# 28_-_PWR_IN_MECH_DOC.net
KiCad netlist of a schematic drawn in Altium Designer
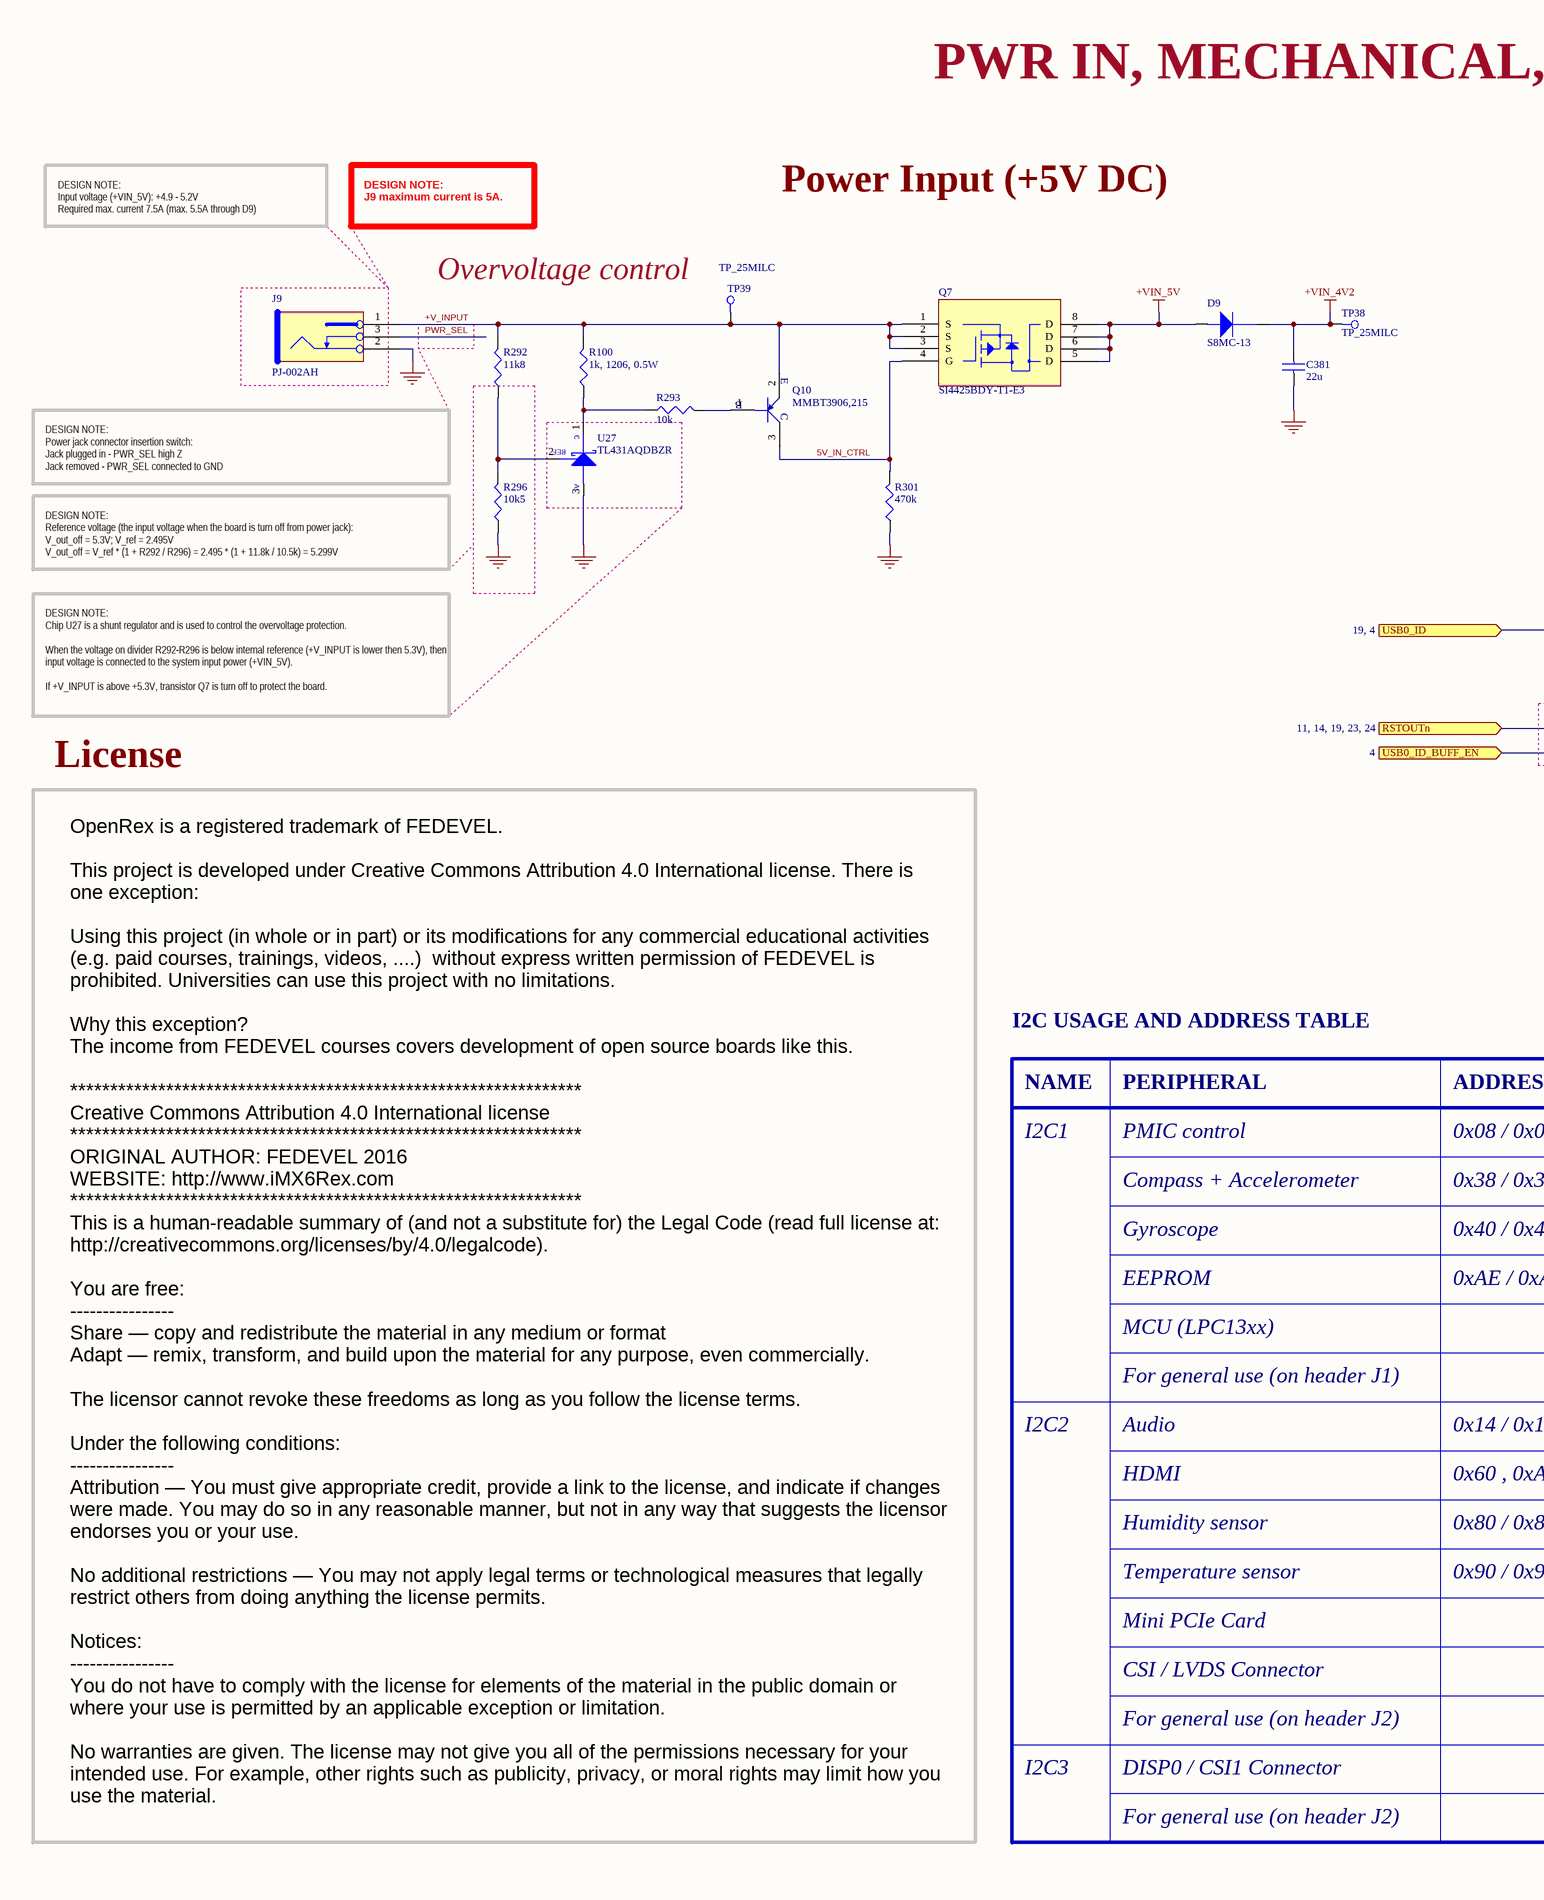
[diagram p0: [28] - PWR IN, MECH, DOC.SchDoc, left]
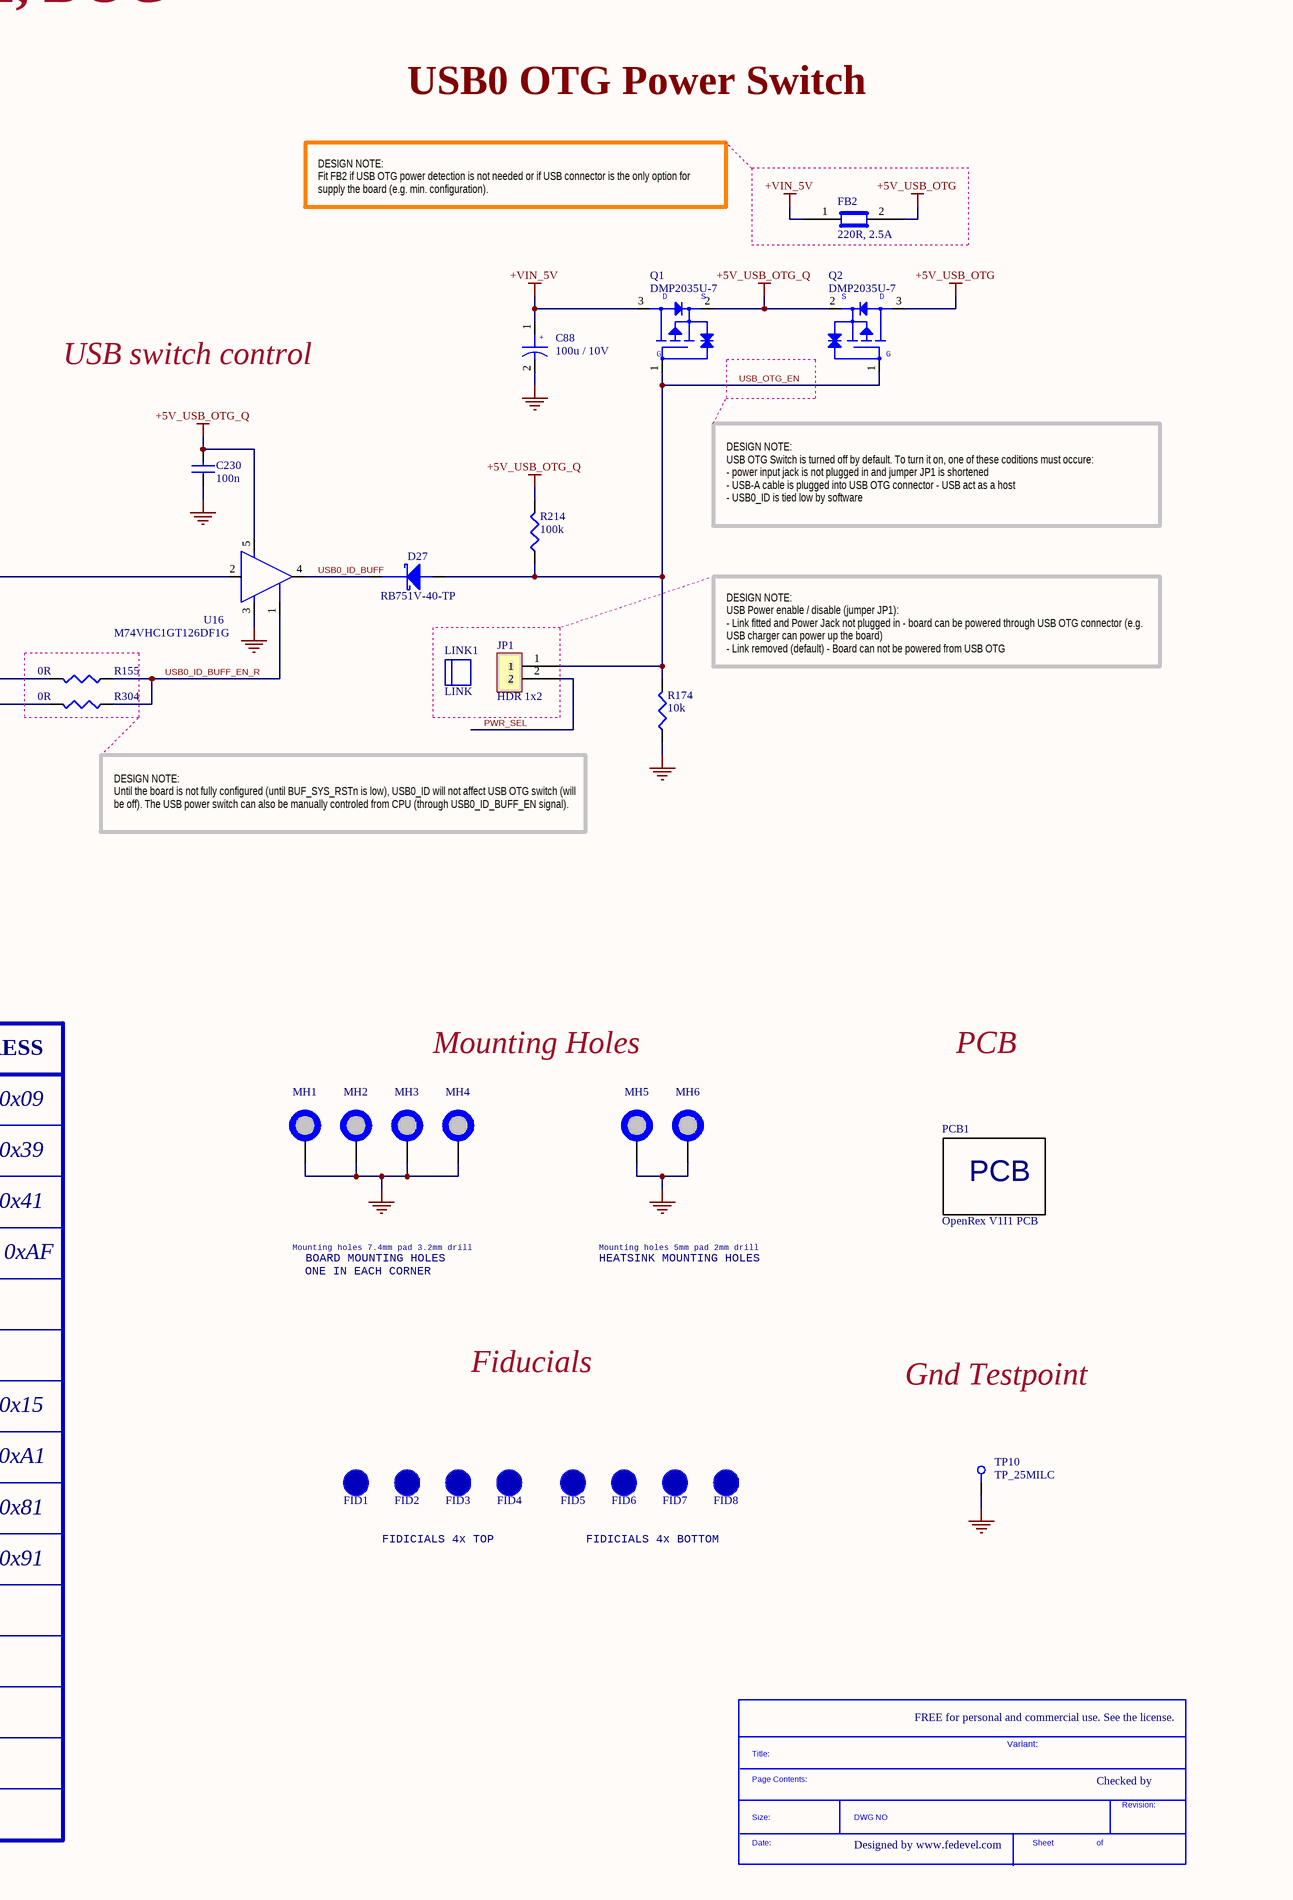
[diagram p1: [28] - PWR IN, MECH, DOC.SchDoc, right]

(export (version "E")
  (design (tool "Eeschema 10.0.6"))
  (components
    (comp (ref "C88")
      (value "100u / 10V")
      (footprint "C2312")
      (description "CAP TANT 100UF 10V 10% 2312")
      (fields
        (field (name "MANUFACTURER") "AVX Corporation")
        (field (name "MANUFACTURER PART NUMBER") "TPSC107K010R0150")
        (field (name ".CREATOR") "MM")
        (field (name ".CHECKED PCB") "MM")
        (field (name ".CHECKED SCH") "MM")
      )
      (libsource (lib "Integrated_Library_FEDEVEL_APR_2015") (part "TPSC107K010R0150"))
    )
    (comp (ref "C230")
      (value "100n")
      (footprint "C0402")
      (description "CAP CER .10UF 50V X5R 10% 0402")
      (fields
        (field (name "MANUFACTURER") "TDK Corporation")
        (field (name "MANUFACTURER PART NUMBER") "C1005X5R1H104K")
      )
      (libsource (lib "Integrated_Library_FEDEVEL_APR_2015") (part "C1005X5R1H104K"))
    )
    (comp (ref "C381")
      (value "22u")
      (footprint "C0603")
      (description "CAP CER 22UF 6.3V 20% X5R 0603")
      (fields
        (field (name "MANUFACTURER") "TDK Corporation")
        (field (name "MANUFACTURER PART NUMBER") "C1608X5R0J226M080AC")
        (field (name ".CREATOR") "MM")
        (field (name ".CHECKED PCB") "MM")
        (field (name ".CHECKED SCH") "MM")
      )
      (libsource (lib "Integrated_Library_FEDEVEL_APR_2015") (part "C1608X5R0J226M080AC"))
    )
    (comp (ref "D9")
      (value "S8MC-13")
      (footprint "SMC")
      (description "DIODE GEN PURP 1KV 8A SMC")
      (fields
        (field (name "MANUFACTURER") "Diodes Incorporated")
        (field (name ".CHECKED PCB") "MM")
        (field (name ".CHECKED SCH") "MM")
        (field (name ".CREATOR") "MM")
      )
      (libsource (lib "Integrated_Library_FEDEVEL_APR_2015") (part "S8MC-13"))
    )
    (comp (ref "D27")
      (value "RB751V-40-TP")
      (footprint "SOD323")
      (description "DIODE SCHTKY 30MA 30V SOD-323")
      (fields (field (name "MANUFACTURER") "Micro Commercial Co"))
      (libsource (lib "Integrated_Library_FEDEVEL_APR_2015") (part "RB751V-40-TP"))
    )
    (comp (ref "FB2")
      (value "220R, 2.5A")
      (footprint "C0603")
      (description "FERRITE CHIP 220 OHM 2500MA 0603")
      (fields
        (field (name "MANUFACTURER") "Murata Electronics North America")
        (field (name "MANUFACTURER PART NUMBER") "BLM18SG221TN1D")
      )
      (libsource (lib "Integrated_Library_FEDEVEL_APR_2015") (part "BLM18SG221TN1D"))
    )
    (comp (ref "FID1")
      (value "FID_1MM_SMALL")
      (footprint "FID_40X52D")
      (description "Fiducial 40mil Diameter, 52mil Mask")
      (libsource (lib "Integrated_Library_FEDEVEL_APR_2015") (part "FID_1MM_SMALL"))
    )
    (comp (ref "FID2")
      (value "FID_1MM_SMALL")
      (footprint "FID_40X52D")
      (description "Fiducial 40mil Diameter, 52mil Mask")
      (libsource (lib "Integrated_Library_FEDEVEL_APR_2015") (part "FID_1MM_SMALL"))
    )
    (comp (ref "FID3")
      (value "FID_1MM_SMALL")
      (footprint "FID_40X52D")
      (description "Fiducial 40mil Diameter, 52mil Mask")
      (libsource (lib "Integrated_Library_FEDEVEL_APR_2015") (part "FID_1MM_SMALL"))
    )
    (comp (ref "FID4")
      (value "FID_1MM_SMALL")
      (footprint "FID_40X52D")
      (description "Fiducial 40mil Diameter, 52mil Mask")
      (libsource (lib "Integrated_Library_FEDEVEL_APR_2015") (part "FID_1MM_SMALL"))
    )
    (comp (ref "FID5")
      (value "FID_1MM_SMALL")
      (footprint "FID_40X52D")
      (description "Fiducial 40mil Diameter, 52mil Mask")
      (libsource (lib "Integrated_Library_FEDEVEL_APR_2015") (part "FID_1MM_SMALL"))
    )
    (comp (ref "FID6")
      (value "FID_1MM_SMALL")
      (footprint "FID_40X52D")
      (description "Fiducial 40mil Diameter, 52mil Mask")
      (libsource (lib "Integrated_Library_FEDEVEL_APR_2015") (part "FID_1MM_SMALL"))
    )
    (comp (ref "FID7")
      (value "FID_1MM_SMALL")
      (footprint "FID_40X52D")
      (description "Fiducial 40mil Diameter, 52mil Mask")
      (libsource (lib "Integrated_Library_FEDEVEL_APR_2015") (part "FID_1MM_SMALL"))
    )
    (comp (ref "FID8")
      (value "FID_1MM_SMALL")
      (footprint "FID_40X52D")
      (description "Fiducial 40mil Diameter, 52mil Mask")
      (libsource (lib "Integrated_Library_FEDEVEL_APR_2015") (part "FID_1MM_SMALL"))
    )
    (comp (ref "J9")
      (value "PJ-002AH")
      (footprint "POWER_JACK_5.5_2.1MM_NS_v1.1")
      (description "CONN PWR JACK 2.1X5.5MM HIGH CUR")
      (fields
        (field (name "MANUFACTURER") "CUI Inc")
        (field (name ".CHECKED PCB") "MM")
        (field (name ".CHECKED SCH") "MM")
        (field (name ".CREATOR") "MM")
      )
      (libsource (lib "Integrated_Library_FEDEVEL_APR_2015") (part "PJ-002AH_v1.1"))
    )
    (comp (ref "JP1")
      (value "HDR 1x2")
      (footprint "HDR_1x2_2.54MM")
      (description "BERGSTIK II .100\" SR STRAIGHT")
      (fields (field (name "MANUFACTURER") "FCI") (field (name "MANUFACTURER PART NUMBER") "68001-202HLF"))
      (libsource (lib "Integrated_Library_FEDEVEL_APR_2015") (part "68001-202HLF"))
    )
    (comp (ref "LINK1")
      (value "LINK")
      (description "CONN JUMPER SHORTING .100\" GOLD")
      (fields
        (field (name "MANUFACTURER") "Sullins Connector Solutions")
        (field (name "MANUFACTURER PART NUMBER") "QPC02SXGN-RC")
      )
      (libsource (lib "Integrated_Library_FEDEVEL_APR_2015") (part "QPC02SXGN-RC"))
    )
    (comp (ref "MH1")
      (value "MH_7.4MMC_3.2MMD")
      (footprint "MH_7.4MMD_3.2MMD")
      (description "Mounting Hole 7.4mm Diameter, 3.2mm Drill")
      (fields (field (name ".CREATOR") "MM"))
      (libsource (lib "Integrated_Library_FEDEVEL_APR_2015") (part "MH_7.4MMC_3.2MMD"))
    )
    (comp (ref "MH2")
      (value "MH_7.4MMC_3.2MMD")
      (footprint "MH_7.4MMD_3.2MMD")
      (description "Mounting Hole 7.4mm Diameter, 3.2mm Drill")
      (fields (field (name ".CREATOR") "MM"))
      (libsource (lib "Integrated_Library_FEDEVEL_APR_2015") (part "MH_7.4MMC_3.2MMD"))
    )
    (comp (ref "MH3")
      (value "MH_7.4MMC_3.2MMD")
      (footprint "MH_7.4MMD_3.2MMD")
      (description "Mounting Hole 7.4mm Diameter, 3.2mm Drill")
      (fields (field (name ".CREATOR") "MM"))
      (libsource (lib "Integrated_Library_FEDEVEL_APR_2015") (part "MH_7.4MMC_3.2MMD"))
    )
    (comp (ref "MH4")
      (value "MH_7.4MMC_3.2MMD")
      (footprint "MH_7.4MMD_3.2MMD")
      (description "Mounting Hole 7.4mm Diameter, 3.2mm Drill")
      (fields (field (name ".CREATOR") "MM"))
      (libsource (lib "Integrated_Library_FEDEVEL_APR_2015") (part "MH_7.4MMC_3.2MMD"))
    )
    (comp (ref "MH5")
      (value "MH_5MMC_2MMD")
      (footprint "MH_5MMD_2MMD")
      (description "Mounting Hole 5mm Diameter, 2mm Drill")
      (fields (field (name ".CREATOR") "MM"))
      (libsource (lib "Integrated_Library_FEDEVEL_APR_2015") (part "MH_5MMC_2MMD"))
    )
    (comp (ref "MH6")
      (value "MH_5MMC_2MMD")
      (footprint "MH_5MMD_2MMD")
      (description "Mounting Hole 5mm Diameter, 2mm Drill")
      (fields (field (name ".CREATOR") "MM"))
      (libsource (lib "Integrated_Library_FEDEVEL_APR_2015") (part "MH_5MMC_2MMD"))
    )
    (comp (ref "PCB1")
      (value "OpenRex V1I1 PCB")
      (fields (field (name ".CREATOR") "MM") (field (name ".CHECKED SCH") "MM"))
      (libsource (lib "Integrated_Library_FEDEVEL_APR_2015") (part "PCB_OpenRex_V1I1"))
    )
    (comp (ref "Q1")
      (value "DMP2035U-7")
      (footprint "SOT-23-3-123")
      (description "MOSFET P-CH 20V 3.6A SOT-23")
      (fields
        (field (name "MANUFACTURER") "Diodes Incorporated")
        (field (name ".CHECKED PCB") "MM")
        (field (name ".CHECKED SCH") "MM")
        (field (name ".CREATOR") "MM")
      )
      (libsource (lib "Integrated_Library_FEDEVEL_APR_2015") (part "DMP2035U-7"))
    )
    (comp (ref "Q2")
      (value "DMP2035U-7")
      (footprint "SOT-23-3-123")
      (description "MOSFET P-CH 20V 3.6A SOT-23")
      (fields
        (field (name "MANUFACTURER") "Diodes Incorporated")
        (field (name ".CHECKED PCB") "MM")
        (field (name ".CHECKED SCH") "MM")
        (field (name ".CREATOR") "MM")
      )
      (libsource (lib "Integrated_Library_FEDEVEL_APR_2015") (part "DMP2035U-7"))
    )
    (comp (ref "Q7")
      (value "SI4425BDY-T1-E3")
      (footprint "8_SOIC_3.9MM")
      (description "MOSFET P-CH 30V 8.8A 8-SOIC")
      (fields
        (field (name "MANUFACTURER") "Vishay Siliconix")
        (field (name ".CHECKED PCB") "MM")
        (field (name ".CHECKED SCH") "MM")
        (field (name ".CREATOR") "MM")
      )
      (libsource (lib "Integrated_Library_FEDEVEL_APR_2015") (part "SI4425BDY-T1-E3"))
    )
    (comp (ref "Q10")
      (value "MMBT3906,215")
      (footprint "SOT-23-3-123")
      (description "TRANS PNP 40V 0.2A SOT23")
      (fields
        (field (name "MANUFACTURER") "NXP Semiconductors")
        (field (name ".CHECKED PCB") "MM")
        (field (name ".CHECKED SCH") "MM")
        (field (name ".CREATOR") "MM")
      )
      (libsource (lib "Integrated_Library_FEDEVEL_APR_2015") (part "MMBT3906,215"))
    )
    (comp (ref "R100")
      (value "1k, 1206, 0.5W")
      (footprint "R1206")
      (description "RES SMD 1K OHM 1% 1/2W 1206")
      (fields
        (field (name "MANUFACTURER") "Stackpole Electronics Inc")
        (field (name "MANUFACTURER PART NUMBER") "RNCP1206FTD1K00")
        (field (name ".CHECKED PCB") "MM")
        (field (name ".CHECKED SCH") "MM")
        (field (name ".CREATOR") "MM")
      )
      (libsource (lib "Integrated_Library_FEDEVEL_APR_2015") (part "RNCP1206FTD1K00"))
    )
    (comp (ref "R155")
      (value "0R")
      (footprint "R0402")
      (description "RES 0.0 OHM 1/16W 0402 SMD")
      (fields
        (field (name "MANUFACTURER") "Yageo")
        (field (name "MANUFACTURER PART NUMBER") "RC0402JR-070RL")
      )
      (libsource (lib "Integrated_Library_FEDEVEL_APR_2015") (part "RC0402JR-070RL"))
    )
    (comp (ref "R174")
      (value "10k")
      (footprint "R0402")
      (description "RES 10.0K OHM 1/16W 1% 0402 SMD")
      (fields
        (field (name "MANUFACTURER") "Yageo")
        (field (name "MANUFACTURER PART NUMBER") "RC0402FR-0710KL")
      )
      (libsource (lib "Integrated_Library_FEDEVEL_APR_2015") (part "RC0402FR-0710KL"))
    )
    (comp (ref "R214")
      (value "100k")
      (footprint "R0402")
      (description "RES 100K OHM 1/16W 1% 0402 SMD")
      (fields
        (field (name "MANUFACTURER") "Stackpole Electronics Inc")
        (field (name "MANUFACTURER PART NUMBER") "RMCF0402FT100K")
      )
      (libsource (lib "Integrated_Library_FEDEVEL_APR_2015") (part "RMCF0402FT100K"))
    )
    (comp (ref "R292")
      (value "11k8")
      (footprint "R0402")
      (description "RES 11.8K OHM 1/16W 1% 0402 SMD")
      (fields
        (field (name "MANUFACTURER") "Vishay Dale")
        (field (name "MANUFACTURER PART NUMBER") "CRCW040211K8FKED")
        (field (name ".CHECKED PCB") "RF")
        (field (name ".CHECKED SCH") "RF")
      )
      (libsource (lib "Integrated_Library_FEDEVEL_APR_2015") (part "CRCW040211K8FKED"))
    )
    (comp (ref "R293")
      (value "10k")
      (footprint "R0402")
      (description "RES 10.0K OHM 1/16W 1% 0402 SMD")
      (fields
        (field (name "MANUFACTURER") "Yageo")
        (field (name "MANUFACTURER PART NUMBER") "RC0402FR-0710KL")
      )
      (libsource (lib "Integrated_Library_FEDEVEL_APR_2015") (part "RC0402FR-0710KL"))
    )
    (comp (ref "R296")
      (value "10k5")
      (footprint "R0402")
      (description "RES 10.5K OHM 1/16W 1% 0402 SMD")
      (fields
        (field (name "MANUFACTURER") "Vishay/Dale")
        (field (name "MANUFACTURER PART NUMBER") "CRCW040210K5FKED")
      )
      (libsource (lib "Integrated_Library_FEDEVEL_APR_2015") (part "CRCW040210K5FKED"))
    )
    (comp (ref "R301")
      (value "470k")
      (footprint "R0402")
      (description "RES 470K OHM 1/16W 1% 0402 SMD")
      (fields
        (field (name "MANUFACTURER") "Vishay Dale")
        (field (name "MANUFACTURER PART NUMBER") "CRCW0402470KFKED")
        (field (name ".CHECKED PCB") "MM")
        (field (name ".CHECKED SCH") "MM")
      )
      (libsource (lib "Integrated_Library_FEDEVEL_APR_2015") (part "CRCW0402470KFKED"))
    )
    (comp (ref "R304")
      (value "0R")
      (footprint "R0402")
      (description "RES 0.0 OHM 1/16W 0402 SMD")
      (fields
        (field (name "MANUFACTURER") "Yageo")
        (field (name "MANUFACTURER PART NUMBER") "RC0402JR-070RL")
      )
      (libsource (lib "Integrated_Library_FEDEVEL_APR_2015") (part "RC0402JR-070RL"))
    )
    (comp (ref "TP10")
      (value "TP_25MILC")
      (footprint "TP_25C")
      (description "Test Point 25mil")
      (libsource (lib "Integrated_Library_FEDEVEL_APR_2015") (part "TP_25MILC"))
    )
    (comp (ref "TP38")
      (value "TP_25MILC")
      (footprint "TP_25C")
      (description "Test Point 25mil")
      (libsource (lib "Integrated_Library_FEDEVEL_APR_2015") (part "TP_25MILC"))
    )
    (comp (ref "TP39")
      (value "TP_25MILC")
      (footprint "TP_25C")
      (description "Test Point 25mil")
      (libsource (lib "Integrated_Library_FEDEVEL_APR_2015") (part "TP_25MILC"))
    )
    (comp (ref "U16")
      (value "M74VHC1GT126DF1G")
      (footprint "SC70_5")
      (description "IC BUFF CMOS LVL/SFTR N-I SOT353")
      (fields
        (field (name "MANUFACTURER") "ON Semiconductor")
        (field (name ".CHECKED PCB") "MM")
        (field (name ".CHECKED SCH") "MM")
        (field (name ".CREATOR") "MM")
      )
      (libsource (lib "Integrated_Library_FEDEVEL_APR_2015") (part "M74VHC1GT126DF1G"))
    )
    (comp (ref "U27")
      (value "TL431AQDBZR")
      (footprint "SOT-23-3-123")
      (description "IC VREF SHUNT ADJ SOT23-3")
      (fields
        (field (name "MANUFACTURER") "Texas Instruments")
        (field (name "TOLERANCE") "±1%")
        (field (name ".CHECKED PCB") "MM")
        (field (name ".CHECKED SCH") "MM")
        (field (name ".CREATOR") "MM")
      )
      (libsource (lib "Integrated_Library_FEDEVEL_APR_2015") (part "TL431AQDBZR"))
    )
  )
  (nets
    (net (code "1") (name "+5V_USB_OTG") (class "Default")
      (node (ref "FB2") (pin "2") (pinfunction "2_2") (pintype "passive"))
      (node (ref "Q2") (pin "3") (pinfunction "3_3") (pintype "passive"))
    )
    (net (code "2") (name "+5V_USB_OTG_Q") (class "Default")
      (node (ref "C230") (pin "2") (pinfunction "2_2") (pintype "passive"))
      (node (ref "Q1") (pin "2") (pinfunction "2_2") (pintype "passive"))
      (node (ref "Q2") (pin "2") (pinfunction "2_2") (pintype "passive"))
      (node (ref "R214") (pin "2") (pinfunction "2_2") (pintype "passive"))
      (node (ref "U16") (pin "5") (pinfunction "VCC_5") (pintype "power_in"))
    )
    (net (code "3") (name "+VIN_4V2") (class "Default")
      (node (ref "C381") (pin "1") (pinfunction "1_1") (pintype "passive"))
      (node (ref "D9") (pin "1") (pinfunction "Cathode_1") (pintype "passive"))
      (node (ref "TP38") (pin "1") (pinfunction "1_1") (pintype "passive"))
    )
    (net (code "4") (name "+VIN_5V") (class "Default")
      (node (ref "C88") (pin "1") (pinfunction "1_1") (pintype "passive"))
      (node (ref "D9") (pin "2") (pinfunction "Anode_2") (pintype "passive"))
      (node (ref "FB2") (pin "1") (pinfunction "1_1") (pintype "passive"))
      (node (ref "Q1") (pin "3") (pinfunction "3_3") (pintype "passive"))
      (node (ref "Q7") (pin "5") (pinfunction "D_5") (pintype "passive"))
      (node (ref "Q7") (pin "6") (pinfunction "D_6") (pintype "passive"))
      (node (ref "Q7") (pin "7") (pinfunction "D_7") (pintype "passive"))
      (node (ref "Q7") (pin "8") (pinfunction "D_8") (pintype "passive"))
    )
    (net (code "5") (name "/+V_INPUT") (class "Default")
      (node (ref "J9") (pin "1") (pinfunction "1_1") (pintype "passive"))
      (node (ref "Q10") (pin "2") (pinfunction "E_2") (pintype "passive"))
      (node (ref "Q7") (pin "1") (pinfunction "S_1") (pintype "passive"))
      (node (ref "Q7") (pin "2") (pinfunction "S_2") (pintype "passive"))
      (node (ref "Q7") (pin "3") (pinfunction "S_3") (pintype "passive"))
      (node (ref "R100") (pin "2") (pinfunction "2_2") (pintype "passive"))
      (node (ref "R292") (pin "2") (pinfunction "2_2") (pintype "passive"))
      (node (ref "TP39") (pin "1") (pinfunction "1_1") (pintype "passive"))
    )
    (net (code "6") (name "/5V_IN_CTRL") (class "Default")
      (node (ref "Q10") (pin "3") (pinfunction "C_3") (pintype "passive"))
      (node (ref "Q7") (pin "4") (pinfunction "G_4") (pintype "passive"))
      (node (ref "R301") (pin "2") (pinfunction "2_2") (pintype "passive"))
    )
    (net (code "7") (name "/PWR_SEL") (class "Default")
      (node (ref "J9") (pin "3") (pinfunction "3_3") (pintype "passive"))
      (node (ref "JP1") (pin "2") (pinfunction "2_2") (pintype "passive"))
    )
    (net (code "8") (name "/RSTOUTn") (class "Default")
      (node (ref "R155") (pin "2") (pinfunction "2_2") (pintype "passive"))
    )
    (net (code "9") (name "/USB0_ID") (class "Default")
      (node (ref "U16") (pin "2") (pinfunction "I_2") (pintype "passive"))
    )
    (net (code "10") (name "/USB0_ID_BUFF") (class "Default")
      (node (ref "D27") (pin "1") (pinfunction "cathode_1") (pintype "passive"))
      (node (ref "U16") (pin "4") (pinfunction "O_4") (pintype "tri_state"))
    )
    (net (code "11") (name "/USB0_ID_BUFF_EN") (class "Default")
      (node (ref "R304") (pin "2") (pinfunction "2_2") (pintype "passive"))
    )
    (net (code "12") (name "/USB0_ID_BUFF_EN_R") (class "Default")
      (node (ref "R155") (pin "1") (pinfunction "1_1") (pintype "passive"))
      (node (ref "R304") (pin "1") (pinfunction "1_1") (pintype "passive"))
      (node (ref "U16") (pin "1") (pinfunction "OE#_1") (pintype "passive"))
    )
    (net (code "13") (name "/USB_OTG_EN") (class "Default")
      (node (ref "D27") (pin "2") (pinfunction "ANODE_2") (pintype "passive"))
      (node (ref "JP1") (pin "1") (pinfunction "1_1") (pintype "passive"))
      (node (ref "Q1") (pin "1") (pinfunction "1_1") (pintype "passive"))
      (node (ref "Q2") (pin "1") (pinfunction "1_1") (pintype "passive"))
      (node (ref "R174") (pin "2") (pinfunction "2_2") (pintype "passive"))
      (node (ref "R214") (pin "1") (pinfunction "1_1") (pintype "passive"))
    )
    (net (code "14") (name "GND") (class "Default")
      (node (ref "C230") (pin "1") (pinfunction "1_1") (pintype "passive"))
      (node (ref "C381") (pin "2") (pinfunction "2_2") (pintype "passive"))
      (node (ref "C88") (pin "2") (pinfunction "2_2") (pintype "passive"))
      (node (ref "J9") (pin "2") (pinfunction "2_2") (pintype "passive"))
      (node (ref "MH1") (pin "1") (pinfunction "1_1") (pintype "passive"))
      (node (ref "MH2") (pin "1") (pinfunction "1_1") (pintype "passive"))
      (node (ref "MH3") (pin "1") (pinfunction "1_1") (pintype "passive"))
      (node (ref "MH4") (pin "1") (pinfunction "1_1") (pintype "passive"))
      (node (ref "MH5") (pin "1") (pinfunction "1_1") (pintype "passive"))
      (node (ref "MH6") (pin "1") (pinfunction "1_1") (pintype "passive"))
      (node (ref "R174") (pin "1") (pinfunction "1_1") (pintype "passive"))
      (node (ref "R296") (pin "1") (pinfunction "1_1") (pintype "passive"))
      (node (ref "R301") (pin "1") (pinfunction "1_1") (pintype "passive"))
      (node (ref "TP10") (pin "1") (pinfunction "1_1") (pintype "passive"))
      (node (ref "U16") (pin "3") (pinfunction "GND_3") (pintype "power_in"))
      (node (ref "U27") (pin "3") (pinfunction "ANODE_3") (pintype "passive"))
    )
    (net (code "15") (name "Net-(Q10-B)") (class "Default")
      (node (ref "Q10") (pin "1") (pinfunction "B_1") (pintype "passive"))
      (node (ref "R293") (pin "2") (pinfunction "2_2") (pintype "passive"))
    )
    (net (code "16") (name "Net-(U27-REF)") (class "Default")
      (node (ref "R292") (pin "1") (pinfunction "1_1") (pintype "passive"))
      (node (ref "R296") (pin "2") (pinfunction "2_2") (pintype "passive"))
      (node (ref "U27") (pin "2") (pinfunction "REF_2") (pintype "passive"))
    )
    (net (code "17") (name "Net-(U27-cathode)") (class "Default")
      (node (ref "R100") (pin "1") (pinfunction "1_1") (pintype "passive"))
      (node (ref "R293") (pin "1") (pinfunction "1_1") (pintype "passive"))
      (node (ref "U27") (pin "1") (pinfunction "cathode_1") (pintype "passive"))
    )
  )
)
